# HMLPGVCA.net
KiCad netlist of a schematic drawn in EAGLE
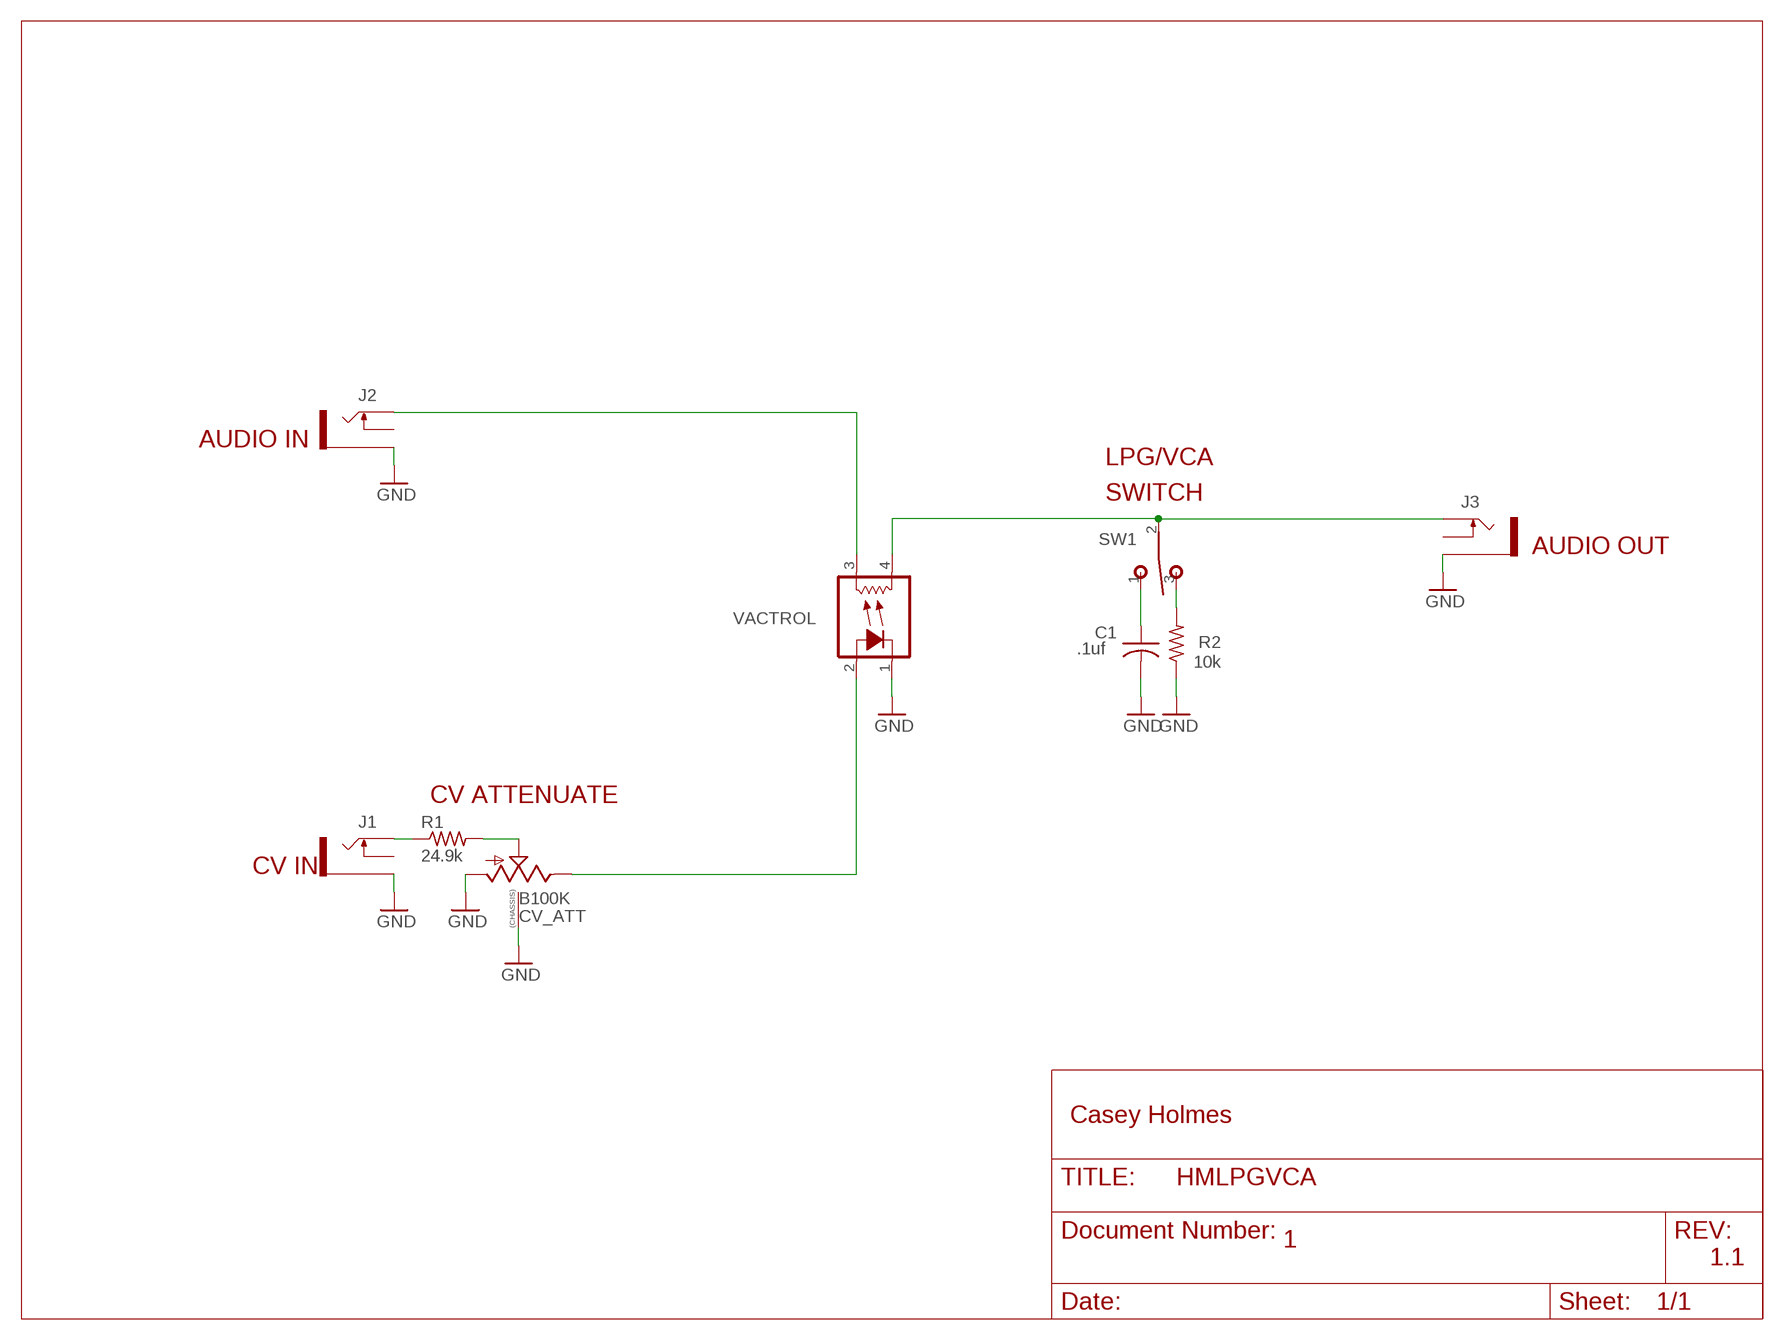
[diagram p0: schematic, sheet 1]

(export (version "E")
  (design (tool "Eeschema 10.0.6"))
  (components
    (comp (ref "C1")
      (value ".1uf")
      (footprint "eagle-import:C0805K")
      (libsource (lib "eagle-import") (part "C-USC0805K"))
    )
    (comp (ref "CV_ATT")
      (value "B100K")
      (footprint "eagle-import:9MM_SNAP-IN_POT")
      (libsource (lib "eagle-import") (part "9MM_SNAP-IN_POT_CHASSIS"))
    )
    (comp (ref "J1")
      (value "THONKICONNNEW")
      (footprint "eagle-import:WQP-PJ301M-12_JACK")
      (libsource (lib "eagle-import") (part "THONKICONNNEW"))
    )
    (comp (ref "J2")
      (value "THONKICONNNEW")
      (footprint "eagle-import:WQP-PJ301M-12_JACK")
      (libsource (lib "eagle-import") (part "THONKICONNNEW"))
    )
    (comp (ref "J3")
      (value "THONKICONNNEW")
      (footprint "eagle-import:WQP-PJ301M-12_JACK")
      (libsource (lib "eagle-import") (part "THONKICONNNEW"))
    )
    (comp (ref "R1")
      (value "24.9k")
      (footprint "eagle-import:R0805")
      (libsource (lib "eagle-import") (part "R-US_R0805"))
    )
    (comp (ref "R2")
      (value "10k")
      (footprint "eagle-import:R0805")
      (libsource (lib "eagle-import") (part "R-US_R0805"))
    )
    (comp (ref "SW1")
      (value "T-80-T-SPDT-ON-OFF-ON")
      (footprint "eagle-import:M9040P")
      (libsource (lib "eagle-import") (part "T-80-T-SPDT-ON-OFF-ON"))
    )
    (comp (ref "VACTROL")
      (value "VACTROL")
      (footprint "eagle-import:VACTROL_4PIN_VTL5C")
      (libsource (lib "eagle-import") (part "VACTROL_4PIN"))
    )
  )
  (nets
    (net (code "1") (name "GND") (class "Default")
      (node (ref "C1") (pin "2") (pinfunction "2_2") (pintype "passive"))
      (node (ref "CV_ATT") (pin "1") (pinfunction "A_1") (pintype "passive"))
      (node (ref "CV_ATT") (pin "CHASSIS1") (pinfunction "P$1_CHASSIS1") (pintype "passive"))
      (node (ref "CV_ATT") (pin "CHASSIS2") (pinfunction "P$1_CHASSIS2") (pintype "passive"))
      (node (ref "J1") (pin "P$3_SLEEVE") (pinfunction "SLEEVE_P$3_SLEEVE") (pintype "passive"))
      (node (ref "J2") (pin "P$3_SLEEVE") (pinfunction "SLEEVE_P$3_SLEEVE") (pintype "passive"))
      (node (ref "J3") (pin "P$3_SLEEVE") (pinfunction "SLEEVE_P$3_SLEEVE") (pintype "passive"))
      (node (ref "R2") (pin "1") (pinfunction "1_1") (pintype "passive"))
      (node (ref "VACTROL") (pin "1") (pinfunction "LED-_1") (pintype "passive"))
    )
    (net (code "2") (name "Net-(CV_ATT-E)") (class "Default")
      (node (ref "CV_ATT") (pin "3") (pinfunction "E_3") (pintype "passive"))
      (node (ref "VACTROL") (pin "2") (pinfunction "LED+_2") (pintype "passive"))
    )
    (net (code "3") (name "Net-(CV_ATT-S)") (class "Default")
      (node (ref "CV_ATT") (pin "2") (pinfunction "S_2") (pintype "passive"))
      (node (ref "R1") (pin "2") (pinfunction "2_2") (pintype "passive"))
    )
    (net (code "4") (name "Net-(J1-TIP)") (class "Default")
      (node (ref "J1") (pin "P$1_TIP") (pinfunction "TIP_P$1_TIP") (pintype "passive"))
      (node (ref "R1") (pin "1") (pinfunction "1_1") (pintype "passive"))
    )
    (net (code "5") (name "Net-(J2-TIP)") (class "Default")
      (node (ref "J2") (pin "P$1_TIP") (pinfunction "TIP_P$1_TIP") (pintype "passive"))
      (node (ref "VACTROL") (pin "3") (pinfunction "RES1_3") (pintype "passive"))
    )
    (net (code "6") (name "Net-(J3-TIP)") (class "Default")
      (node (ref "J3") (pin "P$1_TIP") (pinfunction "TIP_P$1_TIP") (pintype "passive"))
      (node (ref "SW1") (pin "2") (pinfunction "P_2") (pintype "passive"))
      (node (ref "VACTROL") (pin "4") (pinfunction "RES2_4") (pintype "passive"))
    )
    (net (code "7") (name "Net-(SW1-O)") (class "Default")
      (node (ref "C1") (pin "1") (pinfunction "1_1") (pintype "passive"))
      (node (ref "SW1") (pin "1") (pinfunction "O_1") (pintype "passive"))
    )
    (net (code "8") (name "Net-(SW1-S)") (class "Default")
      (node (ref "R2") (pin "2") (pinfunction "2_2") (pintype "passive"))
      (node (ref "SW1") (pin "3") (pinfunction "S_3") (pintype "passive"))
    )
    (net (code "9") (name "unconnected-(J1-SWITCH-PadP$2_SWITCH)") (class "Default")
      (node (ref "J1") (pin "P$2_SWITCH") (pinfunction "SWITCH_P$2_SWITCH") (pintype "passive"))
    )
    (net (code "10") (name "unconnected-(J2-SWITCH-PadP$2_SWITCH)") (class "Default")
      (node (ref "J2") (pin "P$2_SWITCH") (pinfunction "SWITCH_P$2_SWITCH") (pintype "passive"))
    )
    (net (code "11") (name "unconnected-(J3-SWITCH-PadP$2_SWITCH)") (class "Default")
      (node (ref "J3") (pin "P$2_SWITCH") (pinfunction "SWITCH_P$2_SWITCH") (pintype "passive"))
    )
  )
)
